# CNC_Machine_Breakout.net
KiCad netlist of a schematic drawn in Altium Designer
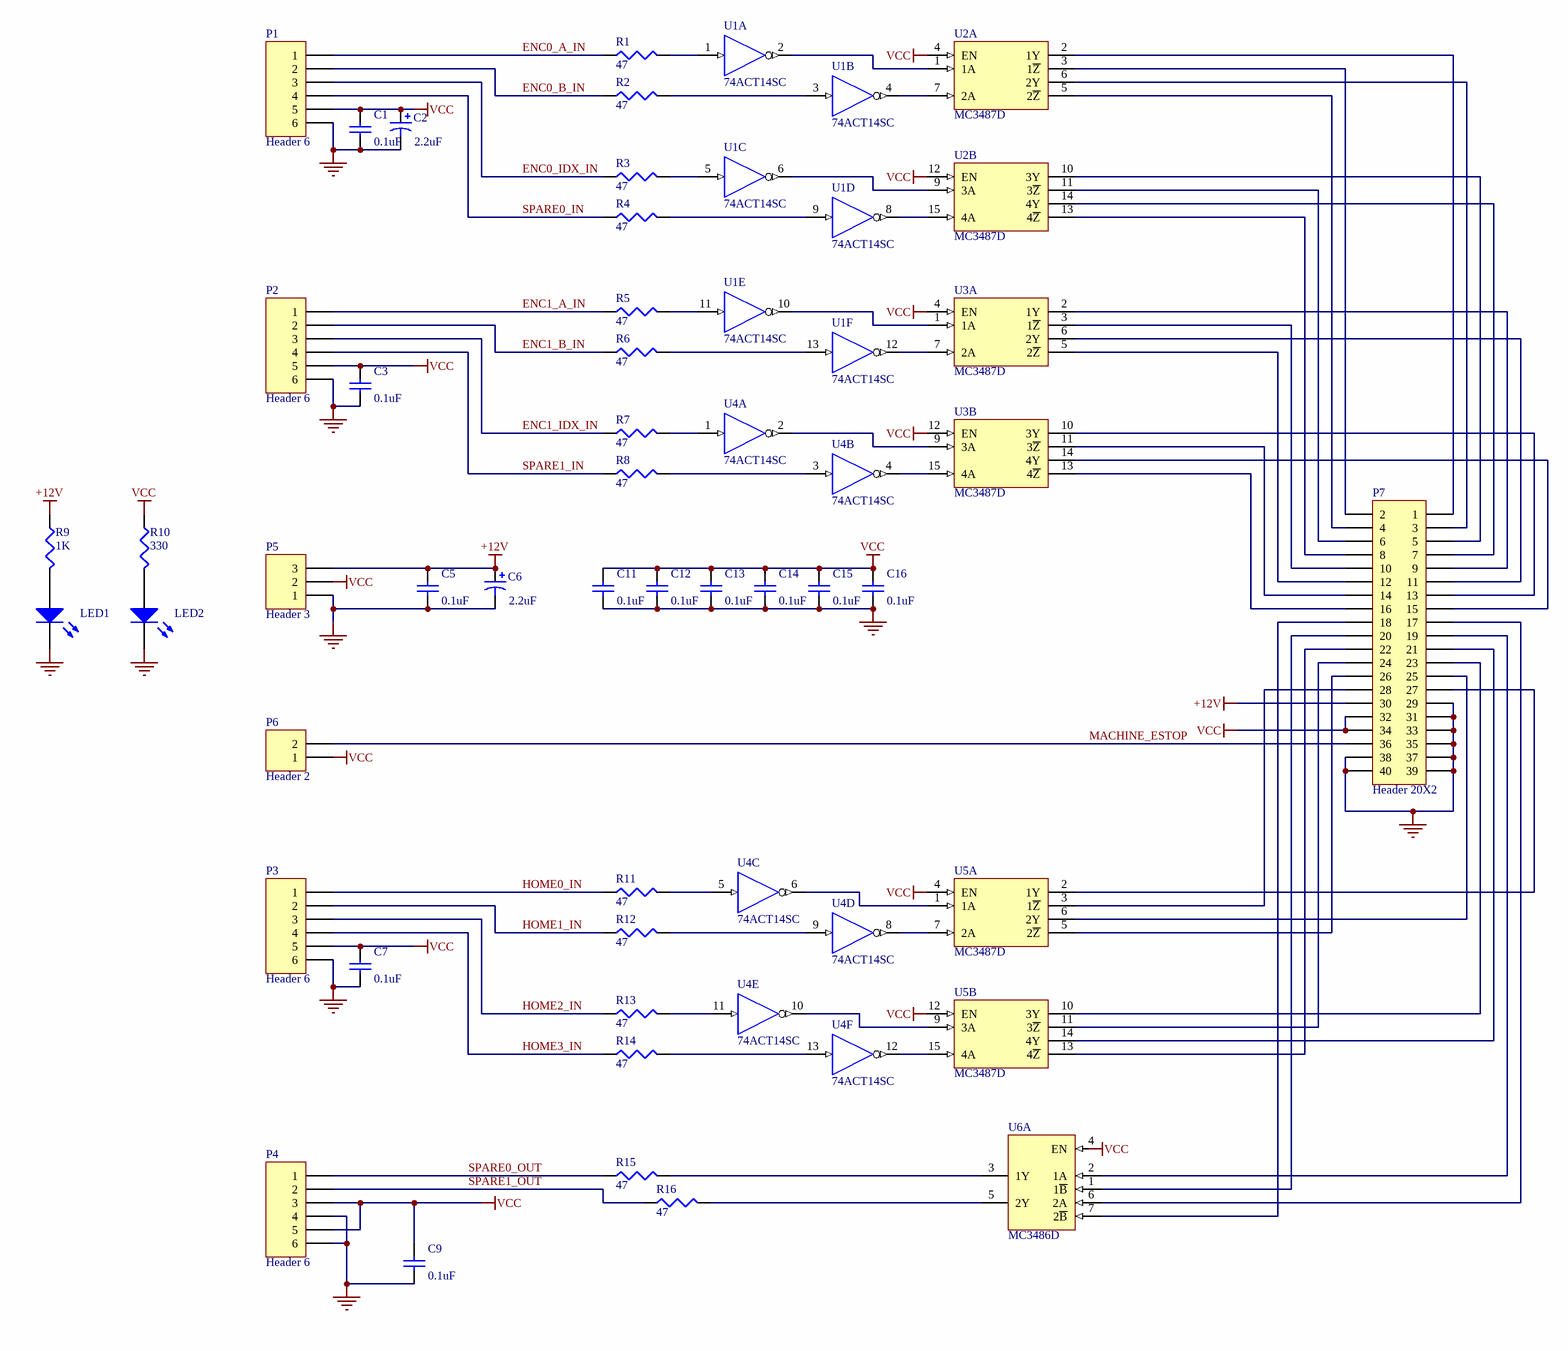
[diagram p0: CNC Machine Breakout.SchDoc]

(export (version "E")
  (design (tool "Eeschema 10.0.6"))
  (components
    (comp (ref "C1")
      (value "0.1uF")
      (footprint "1608[0603]")
      (description "Capacitor (Semiconductor SIM Model)")
      (fields (field (name "Comment") "Cap Semi") (field (name "PUBLISHER") "Altium Limited"))
      (libsource (lib "Miscellaneous Devices") (part "Cap Semi"))
    )
    (comp (ref "C2")
      (value "2.2uF")
      (description "Polarized Capacitor (Surface Mount)")
      (fields (field (name "Comment") "Cap Pol3") (field (name "PUBLISHER") "Altium Limited"))
      (libsource (lib "Miscellaneous Devices") (part "Cap Pol3"))
    )
    (comp (ref "C3")
      (value "0.1uF")
      (footprint "1608[0603]")
      (description "Capacitor (Semiconductor SIM Model)")
      (fields (field (name "Comment") "Cap Semi") (field (name "PUBLISHER") "Altium Limited"))
      (libsource (lib "Miscellaneous Devices") (part "Cap Semi"))
    )
    (comp (ref "C5")
      (value "0.1uF")
      (footprint "1608[0603]")
      (description "Capacitor (Semiconductor SIM Model)")
      (fields (field (name "Comment") "Cap Semi") (field (name "PUBLISHER") "Altium Limited"))
      (libsource (lib "Miscellaneous Devices") (part "Cap Semi"))
    )
    (comp (ref "C6")
      (value "2.2uF")
      (description "Polarized Capacitor (Surface Mount)")
      (fields (field (name "Comment") "Cap Pol3") (field (name "PUBLISHER") "Altium Limited"))
      (libsource (lib "Miscellaneous Devices") (part "Cap Pol3"))
    )
    (comp (ref "C7")
      (value "0.1uF")
      (footprint "1608[0603]")
      (description "Capacitor (Semiconductor SIM Model)")
      (fields (field (name "Comment") "Cap Semi") (field (name "PUBLISHER") "Altium Limited"))
      (libsource (lib "Miscellaneous Devices") (part "Cap Semi"))
    )
    (comp (ref "C9")
      (value "0.1uF")
      (footprint "1608[0603]")
      (description "Capacitor (Semiconductor SIM Model)")
      (fields (field (name "Comment") "Cap Semi") (field (name "PUBLISHER") "Altium Limited"))
      (libsource (lib "Miscellaneous Devices") (part "Cap Semi"))
    )
    (comp (ref "C11")
      (value "0.1uF")
      (footprint "1608[0603]")
      (description "Capacitor (Semiconductor SIM Model)")
      (fields (field (name "Comment") "Cap Semi") (field (name "PUBLISHER") "Altium Limited"))
      (libsource (lib "Miscellaneous Devices") (part "Cap Semi"))
    )
    (comp (ref "C12")
      (value "0.1uF")
      (footprint "1608[0603]")
      (description "Capacitor (Semiconductor SIM Model)")
      (fields (field (name "Comment") "Cap Semi") (field (name "PUBLISHER") "Altium Limited"))
      (libsource (lib "Miscellaneous Devices") (part "Cap Semi"))
    )
    (comp (ref "C13")
      (value "0.1uF")
      (footprint "1608[0603]")
      (description "Capacitor (Semiconductor SIM Model)")
      (fields (field (name "Comment") "Cap Semi") (field (name "PUBLISHER") "Altium Limited"))
      (libsource (lib "Miscellaneous Devices") (part "Cap Semi"))
    )
    (comp (ref "C14")
      (value "0.1uF")
      (footprint "1608[0603]")
      (description "Capacitor (Semiconductor SIM Model)")
      (fields (field (name "Comment") "Cap Semi") (field (name "PUBLISHER") "Altium Limited"))
      (libsource (lib "Miscellaneous Devices") (part "Cap Semi"))
    )
    (comp (ref "C15")
      (value "0.1uF")
      (footprint "1608[0603]")
      (description "Capacitor (Semiconductor SIM Model)")
      (fields (field (name "Comment") "Cap Semi") (field (name "PUBLISHER") "Altium Limited"))
      (libsource (lib "Miscellaneous Devices") (part "Cap Semi"))
    )
    (comp (ref "C16")
      (value "0.1uF")
      (footprint "1608[0603]")
      (description "Capacitor (Semiconductor SIM Model)")
      (fields (field (name "Comment") "Cap Semi") (field (name "PUBLISHER") "Altium Limited"))
      (libsource (lib "Miscellaneous Devices") (part "Cap Semi"))
    )
    (comp (ref "LED1")
      (value "LED3")
      (footprint "CD2012-0805")
      (description "Typical BLUE SiC LED")
      (fields (field (name "PUBLISHER") "Altium Limited"))
      (libsource (lib "Miscellaneous Devices") (part "LED3"))
    )
    (comp (ref "LED2")
      (value "LED3")
      (footprint "CD2012-0805")
      (description "Typical BLUE SiC LED")
      (fields (field (name "PUBLISHER") "Altium Limited"))
      (libsource (lib "Miscellaneous Devices") (part "LED3"))
    )
    (comp (ref "P1")
      (value "Header 6")
      (footprint "OSTVN06A150")
      (description "Header, 6-Pin")
      (fields (field (name "PUBLISHER") "Altium Limited"))
      (libsource (lib "Miscellaneous Connectors") (part "Header 6"))
    )
    (comp (ref "P2")
      (value "Header 6")
      (footprint "OSTVN06A150")
      (description "Header, 6-Pin")
      (fields (field (name "PUBLISHER") "Altium Limited"))
      (libsource (lib "Miscellaneous Connectors") (part "Header 6"))
    )
    (comp (ref "P3")
      (value "Header 6")
      (footprint "OSTVN06A150")
      (description "Header, 6-Pin")
      (fields (field (name "PUBLISHER") "Altium Limited"))
      (libsource (lib "Miscellaneous Connectors") (part "Header 6"))
    )
    (comp (ref "P4")
      (value "Header 6")
      (footprint "OSTVN06A150")
      (description "Header, 6-Pin")
      (fields (field (name "PUBLISHER") "Altium Limited"))
      (libsource (lib "Miscellaneous Connectors") (part "Header 6"))
    )
    (comp (ref "P5")
      (value "Header 3")
      (footprint "OSTVN03A150")
      (description "Header, 3-Pin")
      (fields (field (name "PUBLISHER") "Altium Limited"))
      (libsource (lib "Miscellaneous Connectors") (part "Header 3"))
    )
    (comp (ref "P6")
      (value "Header 2")
      (footprint "OSTVN02A150")
      (description "Header, 2-Pin")
      (fields (field (name "PUBLISHER") "Altium Limited"))
      (libsource (lib "Miscellaneous Connectors") (part "Header 2"))
    )
    (comp (ref "P7")
      (value "Header 20X2")
      (footprint "IDC2.54-V40D")
      (description "Header, 20-Pin, Dual row")
      (fields (field (name "PUBLISHER") "Altium Limited"))
      (libsource (lib "Miscellaneous Connectors") (part "Header 20X2"))
    )
    (comp (ref "R1")
      (value "47")
      (footprint "J1-0603")
      (description "Resistor")
      (fields (field (name "Comment") "Res3") (field (name "PUBLISHER") "Altium Limited"))
      (libsource (lib "Miscellaneous Devices") (part "Res3"))
    )
    (comp (ref "R2")
      (value "47")
      (footprint "J1-0603")
      (description "Resistor")
      (fields (field (name "Comment") "Res3") (field (name "PUBLISHER") "Altium Limited"))
      (libsource (lib "Miscellaneous Devices") (part "Res3"))
    )
    (comp (ref "R3")
      (value "47")
      (footprint "J1-0603")
      (description "Resistor")
      (fields (field (name "Comment") "Res3") (field (name "PUBLISHER") "Altium Limited"))
      (libsource (lib "Miscellaneous Devices") (part "Res3"))
    )
    (comp (ref "R4")
      (value "47")
      (footprint "J1-0603")
      (description "Resistor")
      (fields (field (name "Comment") "Res3") (field (name "PUBLISHER") "Altium Limited"))
      (libsource (lib "Miscellaneous Devices") (part "Res3"))
    )
    (comp (ref "R5")
      (value "47")
      (footprint "J1-0603")
      (description "Resistor")
      (fields (field (name "Comment") "Res3") (field (name "PUBLISHER") "Altium Limited"))
      (libsource (lib "Miscellaneous Devices") (part "Res3"))
    )
    (comp (ref "R6")
      (value "47")
      (footprint "J1-0603")
      (description "Resistor")
      (fields (field (name "Comment") "Res3") (field (name "PUBLISHER") "Altium Limited"))
      (libsource (lib "Miscellaneous Devices") (part "Res3"))
    )
    (comp (ref "R7")
      (value "47")
      (footprint "J1-0603")
      (description "Resistor")
      (fields (field (name "Comment") "Res3") (field (name "PUBLISHER") "Altium Limited"))
      (libsource (lib "Miscellaneous Devices") (part "Res3"))
    )
    (comp (ref "R8")
      (value "47")
      (footprint "J1-0603")
      (description "Resistor")
      (fields (field (name "Comment") "Res3") (field (name "PUBLISHER") "Altium Limited"))
      (libsource (lib "Miscellaneous Devices") (part "Res3"))
    )
    (comp (ref "R9")
      (value "1K")
      (footprint "J1-0603")
      (description "Resistor")
      (fields (field (name "Comment") "Res3") (field (name "PUBLISHER") "Altium Limited"))
      (libsource (lib "Miscellaneous Devices") (part "Res3"))
    )
    (comp (ref "R10")
      (value "330")
      (footprint "J1-0603")
      (description "Resistor")
      (fields (field (name "Comment") "Res3") (field (name "PUBLISHER") "Altium Limited"))
      (libsource (lib "Miscellaneous Devices") (part "Res3"))
    )
    (comp (ref "R11")
      (value "47")
      (footprint "J1-0603")
      (description "Resistor")
      (fields (field (name "Comment") "Res3") (field (name "PUBLISHER") "Altium Limited"))
      (libsource (lib "Miscellaneous Devices") (part "Res3"))
    )
    (comp (ref "R12")
      (value "47")
      (footprint "J1-0603")
      (description "Resistor")
      (fields (field (name "Comment") "Res3") (field (name "PUBLISHER") "Altium Limited"))
      (libsource (lib "Miscellaneous Devices") (part "Res3"))
    )
    (comp (ref "R13")
      (value "47")
      (footprint "J1-0603")
      (description "Resistor")
      (fields (field (name "Comment") "Res3") (field (name "PUBLISHER") "Altium Limited"))
      (libsource (lib "Miscellaneous Devices") (part "Res3"))
    )
    (comp (ref "R14")
      (value "47")
      (footprint "J1-0603")
      (description "Resistor")
      (fields (field (name "Comment") "Res3") (field (name "PUBLISHER") "Altium Limited"))
      (libsource (lib "Miscellaneous Devices") (part "Res3"))
    )
    (comp (ref "R15")
      (value "47")
      (footprint "J1-0603")
      (description "Resistor")
      (fields (field (name "Comment") "Res3") (field (name "PUBLISHER") "Altium Limited"))
      (libsource (lib "Miscellaneous Devices") (part "Res3"))
    )
    (comp (ref "R16")
      (value "47")
      (footprint "J1-0603")
      (description "Resistor")
      (fields (field (name "Comment") "Res3") (field (name "PUBLISHER") "Altium Limited"))
      (libsource (lib "Miscellaneous Devices") (part "Res3"))
    )
    (comp (ref "U1")
      (value "74ACT14SC")
      (footprint "M14A_N")
      (description "Hex Inverter with Schmitt Trigger Input")
      (fields (field (name "PUBLISHER") "Altium Limited"))
      (libsource (lib "FSC Logic Gate") (part "74ACT14SC"))
    )
    (comp (ref "U2")
      (value "MC3487D")
      (footprint "D016_N")
      (description "Quadruple Differential Line Driver with 3-State Output")
      (fields (field (name "PUBLISHER") "Altium Limited"))
      (libsource (lib "TI Interface Line Driver") (part "MC3487D"))
    )
    (comp (ref "U3")
      (value "MC3487D")
      (footprint "D016_N")
      (description "Quadruple Differential Line Driver with 3-State Output")
      (fields (field (name "PUBLISHER") "Altium Limited"))
      (libsource (lib "TI Interface Line Driver") (part "MC3487D"))
    )
    (comp (ref "U4")
      (value "74ACT14SC")
      (footprint "M14A_N")
      (description "Hex Inverter with Schmitt Trigger Input")
      (fields (field (name "PUBLISHER") "Altium Limited"))
      (libsource (lib "FSC Logic Gate") (part "74ACT14SC"))
    )
    (comp (ref "U5")
      (value "MC3487D")
      (footprint "D016_N")
      (description "Quadruple Differential Line Driver with 3-State Output")
      (fields (field (name "PUBLISHER") "Altium Limited"))
      (libsource (lib "TI Interface Line Driver") (part "MC3487D"))
    )
    (comp (ref "U6")
      (value "MC3486D")
      (footprint "D016_N")
      (description "Quadruple Line Receiver with 3-State Output")
      (fields (field (name "PUBLISHER") "Altium Limited"))
      (libsource (lib "TI Interface Line Receiver") (part "MC3486D"))
    )
  )
  (nets
    (net (code "1") (name "+12V") (class "Default")
      (node (ref "C5") (pin "1") (pinfunction "1_1") (pintype "passive"))
      (node (ref "C6") (pin "1") (pinfunction "1_1") (pintype "passive"))
      (node (ref "P5") (pin "3") (pinfunction "3_3") (pintype "passive"))
      (node (ref "P7") (pin "30") (pinfunction "30_30") (pintype "passive"))
      (node (ref "R9") (pin "1") (pinfunction "1_1") (pintype "passive"))
    )
    (net (code "2") (name "/ENC0_A_IN") (class "Default")
      (node (ref "P1") (pin "1") (pinfunction "1_1") (pintype "passive"))
      (node (ref "R1") (pin "1") (pinfunction "1_1") (pintype "passive"))
    )
    (net (code "3") (name "/ENC0_B_IN") (class "Default")
      (node (ref "P1") (pin "2") (pinfunction "2_2") (pintype "passive"))
      (node (ref "R2") (pin "1") (pinfunction "1_1") (pintype "passive"))
    )
    (net (code "4") (name "/ENC0_IDX_IN") (class "Default")
      (node (ref "P1") (pin "3") (pinfunction "3_3") (pintype "passive"))
      (node (ref "R3") (pin "1") (pinfunction "1_1") (pintype "passive"))
    )
    (net (code "5") (name "/ENC1_A_IN") (class "Default")
      (node (ref "P2") (pin "1") (pinfunction "1_1") (pintype "passive"))
      (node (ref "R5") (pin "1") (pinfunction "1_1") (pintype "passive"))
    )
    (net (code "6") (name "/ENC1_B_IN") (class "Default")
      (node (ref "P2") (pin "2") (pinfunction "2_2") (pintype "passive"))
      (node (ref "R6") (pin "1") (pinfunction "1_1") (pintype "passive"))
    )
    (net (code "7") (name "/ENC1_IDX_IN") (class "Default")
      (node (ref "P2") (pin "3") (pinfunction "3_3") (pintype "passive"))
      (node (ref "R7") (pin "1") (pinfunction "1_1") (pintype "passive"))
    )
    (net (code "8") (name "/HOME0_IN") (class "Default")
      (node (ref "P3") (pin "1") (pinfunction "1_1") (pintype "passive"))
      (node (ref "R11") (pin "1") (pinfunction "1_1") (pintype "passive"))
    )
    (net (code "9") (name "/HOME1_IN") (class "Default")
      (node (ref "P3") (pin "2") (pinfunction "2_2") (pintype "passive"))
      (node (ref "R12") (pin "1") (pinfunction "1_1") (pintype "passive"))
    )
    (net (code "10") (name "/HOME2_IN") (class "Default")
      (node (ref "P3") (pin "3") (pinfunction "3_3") (pintype "passive"))
      (node (ref "R13") (pin "1") (pinfunction "1_1") (pintype "passive"))
    )
    (net (code "11") (name "/HOME3_IN") (class "Default")
      (node (ref "P3") (pin "4") (pinfunction "4_4") (pintype "passive"))
      (node (ref "R14") (pin "1") (pinfunction "1_1") (pintype "passive"))
    )
    (net (code "12") (name "/MACHINE_ESTOP") (class "Default")
      (node (ref "P6") (pin "2") (pinfunction "2_2") (pintype "passive"))
      (node (ref "P7") (pin "36") (pinfunction "36_36") (pintype "passive"))
    )
    (net (code "13") (name "/SPARE0_IN") (class "Default")
      (node (ref "P1") (pin "4") (pinfunction "4_4") (pintype "passive"))
      (node (ref "R4") (pin "1") (pinfunction "1_1") (pintype "passive"))
    )
    (net (code "14") (name "/SPARE0_OUT") (class "Default")
      (node (ref "P4") (pin "1") (pinfunction "1_1") (pintype "passive"))
      (node (ref "R15") (pin "1") (pinfunction "1_1") (pintype "passive"))
    )
    (net (code "15") (name "/SPARE1_IN") (class "Default")
      (node (ref "P2") (pin "4") (pinfunction "4_4") (pintype "passive"))
      (node (ref "R8") (pin "1") (pinfunction "1_1") (pintype "passive"))
    )
    (net (code "16") (name "/SPARE1_OUT") (class "Default")
      (node (ref "P4") (pin "2") (pinfunction "2_2") (pintype "passive"))
      (node (ref "R16") (pin "1") (pinfunction "1_1") (pintype "passive"))
    )
    (net (code "17") (name "GND") (class "Default")
      (node (ref "C1") (pin "2") (pinfunction "2_2") (pintype "passive"))
      (node (ref "C11") (pin "2") (pinfunction "2_2") (pintype "passive"))
      (node (ref "C12") (pin "2") (pinfunction "2_2") (pintype "passive"))
      (node (ref "C13") (pin "2") (pinfunction "2_2") (pintype "passive"))
      (node (ref "C14") (pin "2") (pinfunction "2_2") (pintype "passive"))
      (node (ref "C15") (pin "2") (pinfunction "2_2") (pintype "passive"))
      (node (ref "C16") (pin "2") (pinfunction "2_2") (pintype "passive"))
      (node (ref "C2") (pin "2") (pinfunction "2_2") (pintype "passive"))
      (node (ref "C3") (pin "2") (pinfunction "2_2") (pintype "passive"))
      (node (ref "C5") (pin "2") (pinfunction "2_2") (pintype "passive"))
      (node (ref "C6") (pin "2") (pinfunction "2_2") (pintype "passive"))
      (node (ref "C7") (pin "2") (pinfunction "2_2") (pintype "passive"))
      (node (ref "C9") (pin "2") (pinfunction "2_2") (pintype "passive"))
      (node (ref "LED1") (pin "2") (pinfunction "K_2") (pintype "passive"))
      (node (ref "LED2") (pin "2") (pinfunction "K_2") (pintype "passive"))
      (node (ref "P1") (pin "6") (pinfunction "6_6") (pintype "passive"))
      (node (ref "P2") (pin "6") (pinfunction "6_6") (pintype "passive"))
      (node (ref "P3") (pin "6") (pinfunction "6_6") (pintype "passive"))
      (node (ref "P4") (pin "4") (pinfunction "4_4") (pintype "passive"))
      (node (ref "P4") (pin "6") (pinfunction "6_6") (pintype "passive"))
      (node (ref "P5") (pin "1") (pinfunction "1_1") (pintype "passive"))
      (node (ref "P7") (pin "29") (pinfunction "29_29") (pintype "passive"))
      (node (ref "P7") (pin "31") (pinfunction "31_31") (pintype "passive"))
      (node (ref "P7") (pin "33") (pinfunction "33_33") (pintype "passive"))
      (node (ref "P7") (pin "35") (pinfunction "35_35") (pintype "passive"))
      (node (ref "P7") (pin "37") (pinfunction "37_37") (pintype "passive"))
      (node (ref "P7") (pin "38") (pinfunction "38_38") (pintype "passive"))
      (node (ref "P7") (pin "39") (pinfunction "39_39") (pintype "passive"))
      (node (ref "P7") (pin "40") (pinfunction "40_40") (pintype "passive"))
      (node (ref "U1") (pin "7") (pinfunction "GND_7") (pintype "power_in"))
      (node (ref "U2") (pin "8") (pinfunction "GND_8") (pintype "power_in"))
      (node (ref "U3") (pin "8") (pinfunction "GND_8") (pintype "power_in"))
      (node (ref "U4") (pin "7") (pinfunction "GND_7") (pintype "power_in"))
      (node (ref "U5") (pin "8") (pinfunction "GND_8") (pintype "power_in"))
      (node (ref "U6") (pin "8") (pinfunction "GND_8") (pintype "power_in"))
    )
    (net (code "18") (name "Net-(LED1-A)") (class "Default")
      (node (ref "LED1") (pin "1") (pinfunction "A_1") (pintype "passive"))
      (node (ref "R9") (pin "2") (pinfunction "2_2") (pintype "passive"))
    )
    (net (code "19") (name "Net-(LED2-A)") (class "Default")
      (node (ref "LED2") (pin "1") (pinfunction "A_1") (pintype "passive"))
      (node (ref "R10") (pin "2") (pinfunction "2_2") (pintype "passive"))
    )
    (net (code "20") (name "Net-(U1A-I)") (class "Default")
      (node (ref "R1") (pin "2") (pinfunction "2_2") (pintype "passive"))
      (node (ref "U1") (pin "1") (pinfunction "I_1") (pintype "input"))
    )
    (net (code "21") (name "Net-(U1A-~{O})") (class "Default")
      (node (ref "U1") (pin "2") (pinfunction "~{O}_2") (pintype "output"))
      (node (ref "U2") (pin "1") (pinfunction "1A_1") (pintype "input"))
    )
    (net (code "22") (name "Net-(U1B-I)") (class "Default")
      (node (ref "R2") (pin "2") (pinfunction "2_2") (pintype "passive"))
      (node (ref "U1") (pin "3") (pinfunction "I_3") (pintype "input"))
    )
    (net (code "23") (name "Net-(U1B-~{O})") (class "Default")
      (node (ref "U1") (pin "4") (pinfunction "~{O}_4") (pintype "output"))
      (node (ref "U2") (pin "7") (pinfunction "2A_7") (pintype "input"))
    )
    (net (code "24") (name "Net-(U1C-I)") (class "Default")
      (node (ref "R3") (pin "2") (pinfunction "2_2") (pintype "passive"))
      (node (ref "U1") (pin "5") (pinfunction "I_5") (pintype "input"))
    )
    (net (code "25") (name "Net-(U1C-~{O})") (class "Default")
      (node (ref "U1") (pin "6") (pinfunction "~{O}_6") (pintype "output"))
      (node (ref "U2") (pin "9") (pinfunction "3A_9") (pintype "input"))
    )
    (net (code "26") (name "Net-(U1D-I)") (class "Default")
      (node (ref "R4") (pin "2") (pinfunction "2_2") (pintype "passive"))
      (node (ref "U1") (pin "9") (pinfunction "I_9") (pintype "input"))
    )
    (net (code "27") (name "Net-(U1D-~{O})") (class "Default")
      (node (ref "U1") (pin "8") (pinfunction "~{O}_8") (pintype "output"))
      (node (ref "U2") (pin "15") (pinfunction "4A_15") (pintype "input"))
    )
    (net (code "28") (name "Net-(U1E-I)") (class "Default")
      (node (ref "R5") (pin "2") (pinfunction "2_2") (pintype "passive"))
      (node (ref "U1") (pin "11") (pinfunction "I_11") (pintype "input"))
    )
    (net (code "29") (name "Net-(U1E-~{O})") (class "Default")
      (node (ref "U1") (pin "10") (pinfunction "~{O}_10") (pintype "output"))
      (node (ref "U3") (pin "1") (pinfunction "1A_1") (pintype "input"))
    )
    (net (code "30") (name "Net-(U1F-I)") (class "Default")
      (node (ref "R6") (pin "2") (pinfunction "2_2") (pintype "passive"))
      (node (ref "U1") (pin "13") (pinfunction "I_13") (pintype "input"))
    )
    (net (code "31") (name "Net-(U1F-~{O})") (class "Default")
      (node (ref "U1") (pin "12") (pinfunction "~{O}_12") (pintype "output"))
      (node (ref "U3") (pin "7") (pinfunction "2A_7") (pintype "input"))
    )
    (net (code "32") (name "Net-(U2A-1Y)") (class "Default")
      (node (ref "P7") (pin "1") (pinfunction "1_1") (pintype "passive"))
      (node (ref "U2") (pin "2") (pinfunction "1Y_2") (pintype "tri_state"))
    )
    (net (code "33") (name "Net-(U2A-1~{Z})") (class "Default")
      (node (ref "P7") (pin "2") (pinfunction "2_2") (pintype "passive"))
      (node (ref "U2") (pin "3") (pinfunction "1~{Z}_3") (pintype "tri_state"))
    )
    (net (code "34") (name "Net-(U2A-2Y)") (class "Default")
      (node (ref "P7") (pin "3") (pinfunction "3_3") (pintype "passive"))
      (node (ref "U2") (pin "6") (pinfunction "2Y_6") (pintype "tri_state"))
    )
    (net (code "35") (name "Net-(U2A-2~{Z})") (class "Default")
      (node (ref "P7") (pin "4") (pinfunction "4_4") (pintype "passive"))
      (node (ref "U2") (pin "5") (pinfunction "2~{Z}_5") (pintype "tri_state"))
    )
    (net (code "36") (name "Net-(U2B-3Y)") (class "Default")
      (node (ref "P7") (pin "5") (pinfunction "5_5") (pintype "passive"))
      (node (ref "U2") (pin "10") (pinfunction "3Y_10") (pintype "tri_state"))
    )
    (net (code "37") (name "Net-(U2B-3~{Z})") (class "Default")
      (node (ref "P7") (pin "6") (pinfunction "6_6") (pintype "passive"))
      (node (ref "U2") (pin "11") (pinfunction "3~{Z}_11") (pintype "tri_state"))
    )
    (net (code "38") (name "Net-(U2B-4Y)") (class "Default")
      (node (ref "P7") (pin "7") (pinfunction "7_7") (pintype "passive"))
      (node (ref "U2") (pin "14") (pinfunction "4Y_14") (pintype "tri_state"))
    )
    (net (code "39") (name "Net-(U2B-4~{Z})") (class "Default")
      (node (ref "P7") (pin "8") (pinfunction "8_8") (pintype "passive"))
      (node (ref "U2") (pin "13") (pinfunction "4~{Z}_13") (pintype "tri_state"))
    )
    (net (code "40") (name "Net-(U3A-1Y)") (class "Default")
      (node (ref "P7") (pin "9") (pinfunction "9_9") (pintype "passive"))
      (node (ref "U3") (pin "2") (pinfunction "1Y_2") (pintype "tri_state"))
    )
    (net (code "41") (name "Net-(U3A-1~{Z})") (class "Default")
      (node (ref "P7") (pin "10") (pinfunction "10_10") (pintype "passive"))
      (node (ref "U3") (pin "3") (pinfunction "1~{Z}_3") (pintype "tri_state"))
    )
    (net (code "42") (name "Net-(U3A-2Y)") (class "Default")
      (node (ref "P7") (pin "11") (pinfunction "11_11") (pintype "passive"))
      (node (ref "U3") (pin "6") (pinfunction "2Y_6") (pintype "tri_state"))
    )
    (net (code "43") (name "Net-(U3A-2~{Z})") (class "Default")
      (node (ref "P7") (pin "12") (pinfunction "12_12") (pintype "passive"))
      (node (ref "U3") (pin "5") (pinfunction "2~{Z}_5") (pintype "tri_state"))
    )
    (net (code "44") (name "Net-(U3B-3A)") (class "Default")
      (node (ref "U3") (pin "9") (pinfunction "3A_9") (pintype "input"))
      (node (ref "U4") (pin "2") (pinfunction "~{O}_2") (pintype "output"))
    )
    (net (code "45") (name "Net-(U3B-3Y)") (class "Default")
      (node (ref "P7") (pin "13") (pinfunction "13_13") (pintype "passive"))
      (node (ref "U3") (pin "10") (pinfunction "3Y_10") (pintype "tri_state"))
    )
    (net (code "46") (name "Net-(U3B-3~{Z})") (class "Default")
      (node (ref "P7") (pin "14") (pinfunction "14_14") (pintype "passive"))
      (node (ref "U3") (pin "11") (pinfunction "3~{Z}_11") (pintype "tri_state"))
    )
    (net (code "47") (name "Net-(U3B-4A)") (class "Default")
      (node (ref "U3") (pin "15") (pinfunction "4A_15") (pintype "input"))
      (node (ref "U4") (pin "4") (pinfunction "~{O}_4") (pintype "output"))
    )
    (net (code "48") (name "Net-(U3B-4Y)") (class "Default")
      (node (ref "P7") (pin "15") (pinfunction "15_15") (pintype "passive"))
      (node (ref "U3") (pin "14") (pinfunction "4Y_14") (pintype "tri_state"))
    )
    (net (code "49") (name "Net-(U3B-4~{Z})") (class "Default")
      (node (ref "P7") (pin "16") (pinfunction "16_16") (pintype "passive"))
      (node (ref "U3") (pin "13") (pinfunction "4~{Z}_13") (pintype "tri_state"))
    )
    (net (code "50") (name "Net-(U4A-I)") (class "Default")
      (node (ref "R7") (pin "2") (pinfunction "2_2") (pintype "passive"))
      (node (ref "U4") (pin "1") (pinfunction "I_1") (pintype "input"))
    )
    (net (code "51") (name "Net-(U4B-I)") (class "Default")
      (node (ref "R8") (pin "2") (pinfunction "2_2") (pintype "passive"))
      (node (ref "U4") (pin "3") (pinfunction "I_3") (pintype "input"))
    )
    (net (code "52") (name "Net-(U4C-I)") (class "Default")
      (node (ref "R11") (pin "2") (pinfunction "2_2") (pintype "passive"))
      (node (ref "U4") (pin "5") (pinfunction "I_5") (pintype "input"))
    )
    (net (code "53") (name "Net-(U4C-~{O})") (class "Default")
      (node (ref "U4") (pin "6") (pinfunction "~{O}_6") (pintype "output"))
      (node (ref "U5") (pin "1") (pinfunction "1A_1") (pintype "input"))
    )
    (net (code "54") (name "Net-(U4D-I)") (class "Default")
      (node (ref "R12") (pin "2") (pinfunction "2_2") (pintype "passive"))
      (node (ref "U4") (pin "9") (pinfunction "I_9") (pintype "input"))
    )
    (net (code "55") (name "Net-(U4D-~{O})") (class "Default")
      (node (ref "U4") (pin "8") (pinfunction "~{O}_8") (pintype "output"))
      (node (ref "U5") (pin "7") (pinfunction "2A_7") (pintype "input"))
    )
    (net (code "56") (name "Net-(U4E-I)") (class "Default")
      (node (ref "R13") (pin "2") (pinfunction "2_2") (pintype "passive"))
      (node (ref "U4") (pin "11") (pinfunction "I_11") (pintype "input"))
    )
    (net (code "57") (name "Net-(U4E-~{O})") (class "Default")
      (node (ref "U4") (pin "10") (pinfunction "~{O}_10") (pintype "output"))
      (node (ref "U5") (pin "9") (pinfunction "3A_9") (pintype "input"))
    )
    (net (code "58") (name "Net-(U4F-I)") (class "Default")
      (node (ref "R14") (pin "2") (pinfunction "2_2") (pintype "passive"))
      (node (ref "U4") (pin "13") (pinfunction "I_13") (pintype "input"))
    )
    (net (code "59") (name "Net-(U4F-~{O})") (class "Default")
      (node (ref "U4") (pin "12") (pinfunction "~{O}_12") (pintype "output"))
      (node (ref "U5") (pin "15") (pinfunction "4A_15") (pintype "input"))
    )
    (net (code "60") (name "Net-(U5A-1Y)") (class "Default")
      (node (ref "P7") (pin "27") (pinfunction "27_27") (pintype "passive"))
      (node (ref "U5") (pin "2") (pinfunction "1Y_2") (pintype "tri_state"))
    )
    (net (code "61") (name "Net-(U5A-1~{Z})") (class "Default")
      (node (ref "P7") (pin "28") (pinfunction "28_28") (pintype "passive"))
      (node (ref "U5") (pin "3") (pinfunction "1~{Z}_3") (pintype "tri_state"))
    )
    (net (code "62") (name "Net-(U5A-2Y)") (class "Default")
      (node (ref "P7") (pin "25") (pinfunction "25_25") (pintype "passive"))
      (node (ref "U5") (pin "6") (pinfunction "2Y_6") (pintype "tri_state"))
    )
    (net (code "63") (name "Net-(U5A-2~{Z})") (class "Default")
      (node (ref "P7") (pin "26") (pinfunction "26_26") (pintype "passive"))
      (node (ref "U5") (pin "5") (pinfunction "2~{Z}_5") (pintype "tri_state"))
    )
    (net (code "64") (name "Net-(U5B-3Y)") (class "Default")
      (node (ref "P7") (pin "23") (pinfunction "23_23") (pintype "passive"))
      (node (ref "U5") (pin "10") (pinfunction "3Y_10") (pintype "tri_state"))
    )
    (net (code "65") (name "Net-(U5B-3~{Z})") (class "Default")
      (node (ref "P7") (pin "24") (pinfunction "24_24") (pintype "passive"))
      (node (ref "U5") (pin "11") (pinfunction "3~{Z}_11") (pintype "tri_state"))
    )
    (net (code "66") (name "Net-(U5B-4Y)") (class "Default")
      (node (ref "P7") (pin "21") (pinfunction "21_21") (pintype "passive"))
      (node (ref "U5") (pin "14") (pinfunction "4Y_14") (pintype "tri_state"))
    )
    (net (code "67") (name "Net-(U5B-4~{Z})") (class "Default")
      (node (ref "P7") (pin "22") (pinfunction "22_22") (pintype "passive"))
      (node (ref "U5") (pin "13") (pinfunction "4~{Z}_13") (pintype "tri_state"))
    )
    (net (code "68") (name "Net-(U6A-1A)") (class "Default")
      (node (ref "P7") (pin "19") (pinfunction "19_19") (pintype "passive"))
      (node (ref "U6") (pin "2") (pinfunction "1A_2") (pintype "input"))
    )
    (net (code "69") (name "Net-(U6A-1Y)") (class "Default")
      (node (ref "R15") (pin "2") (pinfunction "2_2") (pintype "passive"))
      (node (ref "U6") (pin "3") (pinfunction "1Y_3") (pintype "tri_state"))
    )
    (net (code "70") (name "Net-(U6A-1~{B})") (class "Default")
      (node (ref "P7") (pin "20") (pinfunction "20_20") (pintype "passive"))
      (node (ref "U6") (pin "1") (pinfunction "1~{B}_1") (pintype "input"))
    )
    (net (code "71") (name "Net-(U6A-2A)") (class "Default")
      (node (ref "P7") (pin "17") (pinfunction "17_17") (pintype "passive"))
      (node (ref "U6") (pin "6") (pinfunction "2A_6") (pintype "input"))
    )
    (net (code "72") (name "Net-(U6A-2Y)") (class "Default")
      (node (ref "R16") (pin "2") (pinfunction "2_2") (pintype "passive"))
      (node (ref "U6") (pin "5") (pinfunction "2Y_5") (pintype "tri_state"))
    )
    (net (code "73") (name "Net-(U6A-2~{B})") (class "Default")
      (node (ref "P7") (pin "18") (pinfunction "18_18") (pintype "passive"))
      (node (ref "U6") (pin "7") (pinfunction "2~{B}_7") (pintype "input"))
    )
    (net (code "74") (name "VCC") (class "Default")
      (node (ref "C1") (pin "1") (pinfunction "1_1") (pintype "passive"))
      (node (ref "C11") (pin "1") (pinfunction "1_1") (pintype "passive"))
      (node (ref "C12") (pin "1") (pinfunction "1_1") (pintype "passive"))
      (node (ref "C13") (pin "1") (pinfunction "1_1") (pintype "passive"))
      (node (ref "C14") (pin "1") (pinfunction "1_1") (pintype "passive"))
      (node (ref "C15") (pin "1") (pinfunction "1_1") (pintype "passive"))
      (node (ref "C16") (pin "1") (pinfunction "1_1") (pintype "passive"))
      (node (ref "C2") (pin "1") (pinfunction "1_1") (pintype "passive"))
      (node (ref "C3") (pin "1") (pinfunction "1_1") (pintype "passive"))
      (node (ref "C7") (pin "1") (pinfunction "1_1") (pintype "passive"))
      (node (ref "C9") (pin "1") (pinfunction "1_1") (pintype "passive"))
      (node (ref "P1") (pin "5") (pinfunction "5_5") (pintype "passive"))
      (node (ref "P2") (pin "5") (pinfunction "5_5") (pintype "passive"))
      (node (ref "P3") (pin "5") (pinfunction "5_5") (pintype "passive"))
      (node (ref "P4") (pin "3") (pinfunction "3_3") (pintype "passive"))
      (node (ref "P4") (pin "5") (pinfunction "5_5") (pintype "passive"))
      (node (ref "P5") (pin "2") (pinfunction "2_2") (pintype "passive"))
      (node (ref "P6") (pin "1") (pinfunction "1_1") (pintype "passive"))
      (node (ref "P7") (pin "32") (pinfunction "32_32") (pintype "passive"))
      (node (ref "P7") (pin "34") (pinfunction "34_34") (pintype "passive"))
      (node (ref "R10") (pin "1") (pinfunction "1_1") (pintype "passive"))
      (node (ref "U1") (pin "14") (pinfunction "VCC_14") (pintype "power_in"))
      (node (ref "U2") (pin "12") (pinfunction "EN_12") (pintype "input"))
      (node (ref "U2") (pin "16") (pinfunction "VCC_16") (pintype "power_in"))
      (node (ref "U2") (pin "4") (pinfunction "EN_4") (pintype "input"))
      (node (ref "U3") (pin "12") (pinfunction "EN_12") (pintype "input"))
      (node (ref "U3") (pin "16") (pinfunction "VCC_16") (pintype "power_in"))
      (node (ref "U3") (pin "4") (pinfunction "EN_4") (pintype "input"))
      (node (ref "U4") (pin "14") (pinfunction "VCC_14") (pintype "power_in"))
      (node (ref "U5") (pin "12") (pinfunction "EN_12") (pintype "input"))
      (node (ref "U5") (pin "16") (pinfunction "VCC_16") (pintype "power_in"))
      (node (ref "U5") (pin "4") (pinfunction "EN_4") (pintype "input"))
      (node (ref "U6") (pin "16") (pinfunction "VCC_16") (pintype "power_in"))
    )
    (net (code "75") (name "unconnected-(U6A-EN-Pad4)") (class "Default")
      (node (ref "U6") (pin "4") (pinfunction "EN_4") (pintype "input"))
    )
  )
)
